# Auxiliary.net
KiCad netlist of a schematic drawn in Altium Designer
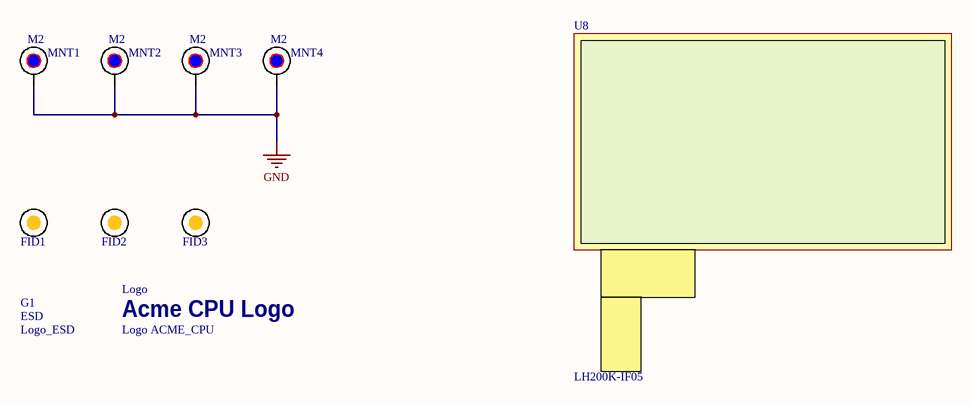
[diagram p0: Auxiliary.SchDoc]

(export (version "E")
  (design (tool "Eeschema 10.0.6"))
  (components
    (comp (ref "FID1")
      (value "N/A")
      (footprint "Fiducial")
      (description "Fiducial mark.  There is nothing to buy or mount.")
      (libsource (lib "altium-import") (part "root_0_Fiducial_"))
    )
    (comp (ref "FID2")
      (value "N/A")
      (footprint "Fiducial")
      (description "Fiducial mark.  There is nothing to buy or mount.")
      (libsource (lib "altium-import") (part "root_0_Fiducial_"))
    )
    (comp (ref "FID3")
      (value "N/A")
      (footprint "Fiducial")
      (description "Fiducial mark.  There is nothing to buy or mount.")
      (libsource (lib "altium-import") (part "root_0_Fiducial_"))
    )
    (comp (ref "G1")
      (value "Logo_ESD")
      (footprint "Logo_ESD")
      (libsource (lib "altium-import") (part "root_0_Logo_ESD_"))
    )
    (comp (ref "Logo")
      (value "Logo ACME_CPU")
      (footprint "LOGO_ACME_CPU")
      (libsource (lib "BLDC_Motor_Driver") (part "Logo ACME_CPU"))
    )
    (comp (ref "MNT1")
      (value "MountHole M2. Nothing to buy or mount")
      (footprint "MountHole_M2")
      (description "PCB Mount Hole. There is nothing to buy or mount.")
      (libsource (lib "BLDC_Motor_Driver") (part "MountHole_M2"))
    )
    (comp (ref "MNT2")
      (value "MountHole M2. Nothing to buy or mount")
      (footprint "MountHole_M2")
      (description "PCB Mount Hole. There is nothing to buy or mount.")
      (libsource (lib "BLDC_Motor_Driver") (part "MountHole_M2"))
    )
    (comp (ref "MNT3")
      (value "MountHole M2. Nothing to buy or mount")
      (footprint "MountHole_M2")
      (description "PCB Mount Hole. There is nothing to buy or mount.")
      (libsource (lib "BLDC_Motor_Driver") (part "MountHole_M2"))
    )
    (comp (ref "MNT4")
      (value "MountHole M2. Nothing to buy or mount")
      (footprint "MountHole_M2")
      (description "PCB Mount Hole. There is nothing to buy or mount.")
      (libsource (lib "BLDC_Motor_Driver") (part "MountHole_M2"))
    )
    (comp (ref "U8")
      (value "LH200K-IF05")
      (description "2” TFT LCD Display.")
      (fields (field (name "MANUFACTURER") "Shenzhen Limito Technology Inc."))
      (libsource (lib "BLDC_Motor_Driver") (part "MOD LH200K-IF05 240x320 2-inch TFT LCD Display"))
    )
  )
  (nets
    (net (code "1") (name "GND") (class "Default")
      (node (ref "MNT1") (pin "1") (pintype "passive"))
      (node (ref "MNT2") (pin "1") (pintype "passive"))
      (node (ref "MNT3") (pin "1") (pintype "passive"))
      (node (ref "MNT4") (pin "1") (pintype "passive"))
    )
  )
)
